# FPGA_Expansion.net
KiCad netlist of a schematic drawn in Altium Designer
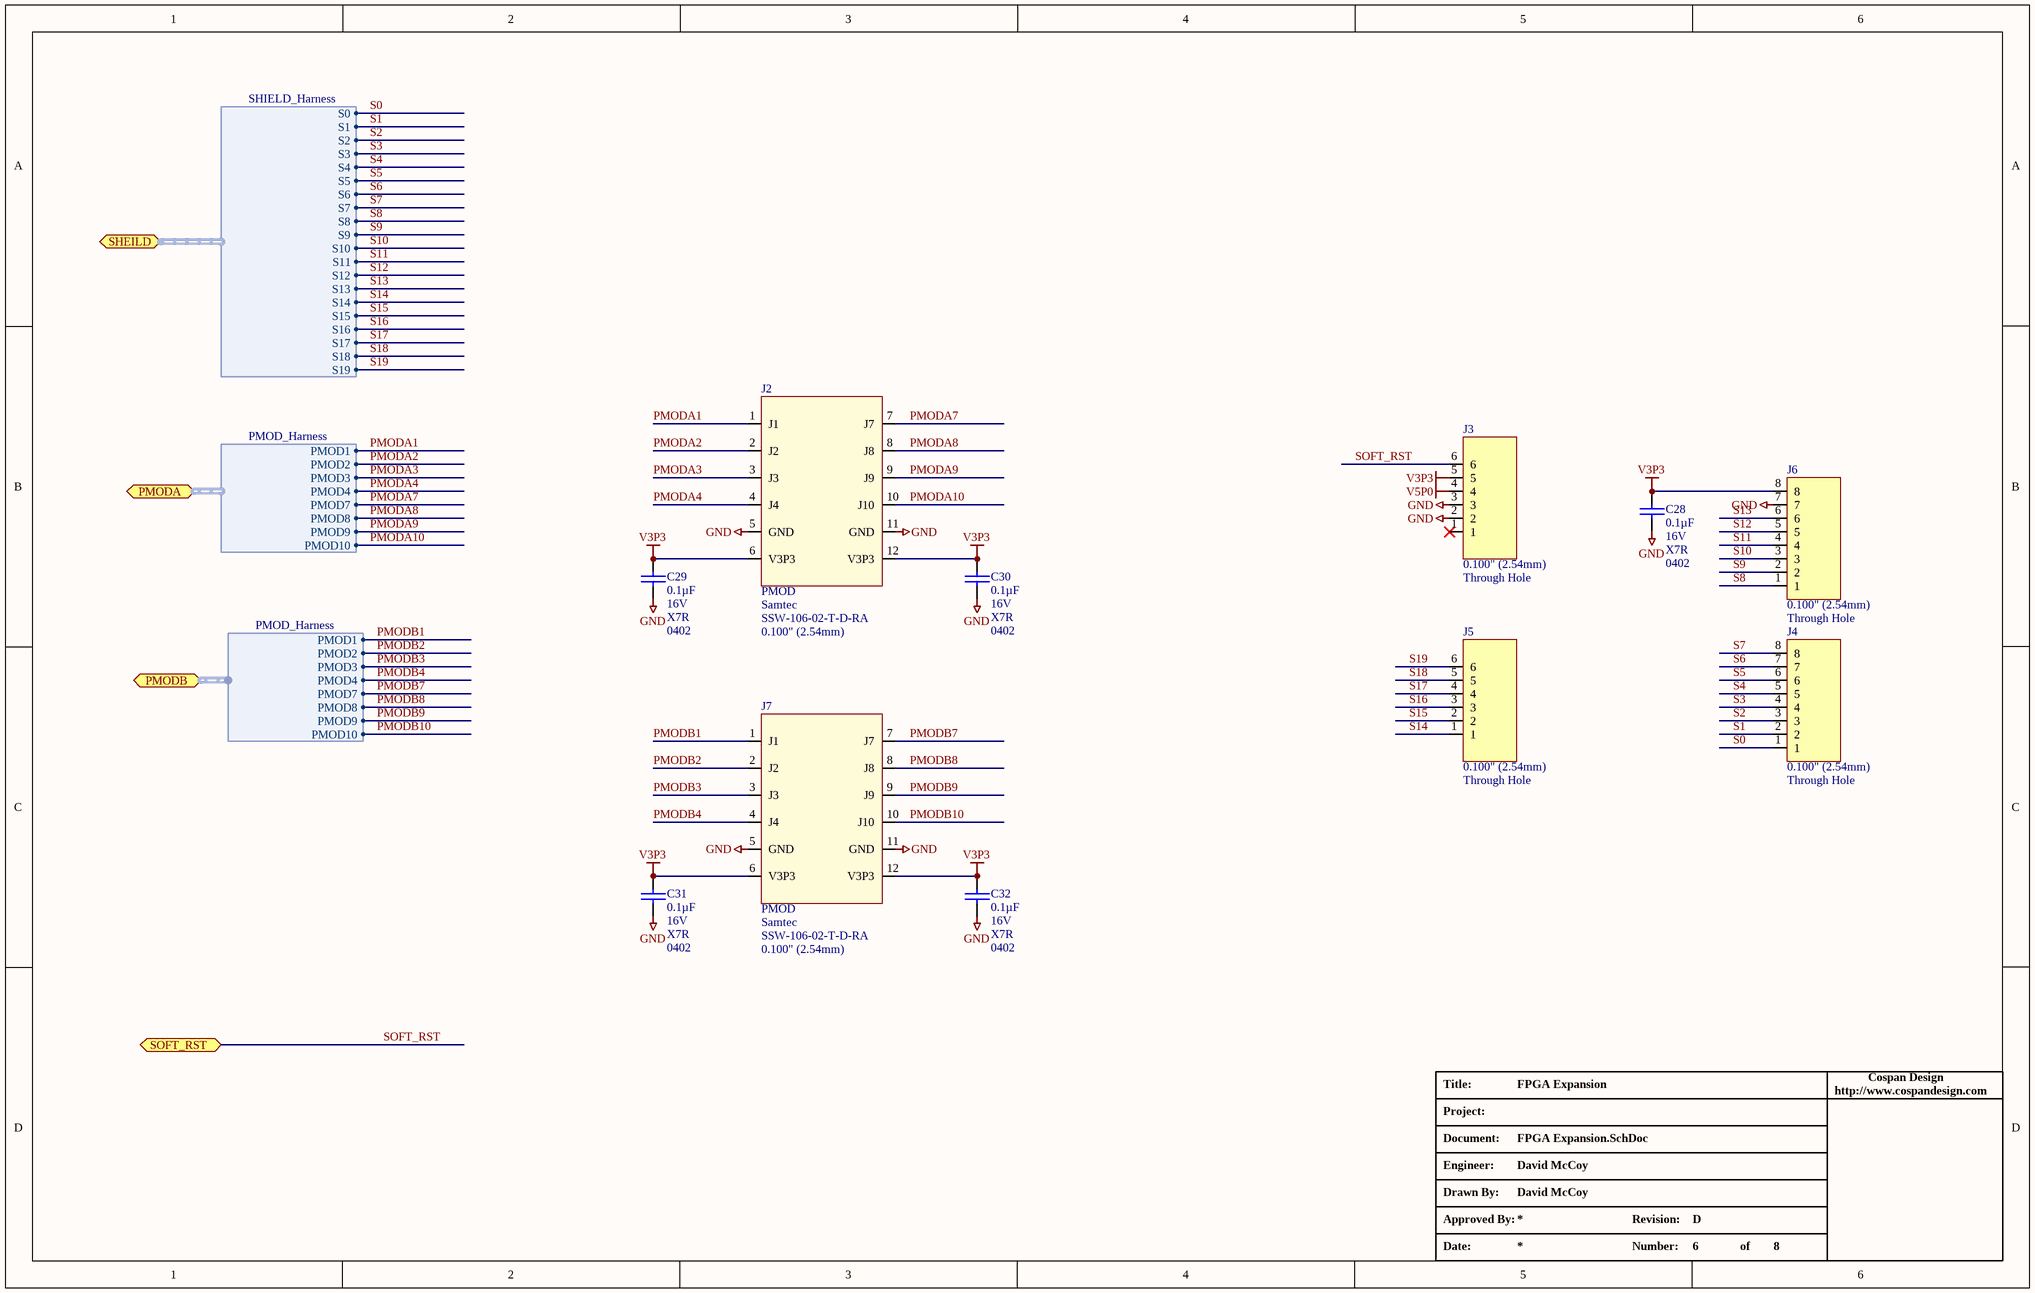
[diagram p0: FPGA Expansion.SchDoc]

(export (version "E")
  (design (tool "Eeschema 10.0.6"))
  (components
    (comp (ref "C28")
      (value "0.1uF")
      (footprint "C_ERA-0402")
      (description "CAP CER .10UF 16V X7R 0402")
      (fields
        (field (name "MANUFACTURER") "TDK Corporation")
        (field (name "MANUFACTURER PART NUMBER") "C1005X7R1C104K")
        (field (name "CAPACITANCE") "0.1µF")
        (field (name "VOLTAGE - RATED") "16V")
        (field (name "TEMPERATURE COEFFICIENT") "X7R")
        (field (name "PACKAGE / CASE") "0402")
      )
      (libsource (lib "Main LibraryX") (part "C_0402_0.1UF_16V"))
    )
    (comp (ref "C29")
      (value "0.1uF")
      (footprint "C_ERA-0402")
      (description "CAP CER .10UF 16V X7R 0402")
      (fields
        (field (name "MANUFACTURER") "TDK Corporation")
        (field (name "MANUFACTURER PART NUMBER") "C1005X7R1C104K")
        (field (name "CAPACITANCE") "0.1µF")
        (field (name "VOLTAGE - RATED") "16V")
        (field (name "TEMPERATURE COEFFICIENT") "X7R")
        (field (name "PACKAGE / CASE") "0402")
      )
      (libsource (lib "Main LibraryX") (part "C_0402_0.1UF_16V"))
    )
    (comp (ref "C30")
      (value "0.1uF")
      (footprint "C_ERA-0402")
      (description "CAP CER .10UF 16V X7R 0402")
      (fields
        (field (name "MANUFACTURER") "TDK Corporation")
        (field (name "MANUFACTURER PART NUMBER") "C1005X7R1C104K")
        (field (name "CAPACITANCE") "0.1µF")
        (field (name "VOLTAGE - RATED") "16V")
        (field (name "TEMPERATURE COEFFICIENT") "X7R")
        (field (name "PACKAGE / CASE") "0402")
      )
      (libsource (lib "Main LibraryX") (part "C_0402_0.1UF_16V"))
    )
    (comp (ref "C31")
      (value "0.1uF")
      (footprint "C_ERA-0402")
      (description "CAP CER .10UF 16V X7R 0402")
      (fields
        (field (name "MANUFACTURER") "TDK Corporation")
        (field (name "MANUFACTURER PART NUMBER") "C1005X7R1C104K")
        (field (name "CAPACITANCE") "0.1µF")
        (field (name "VOLTAGE - RATED") "16V")
        (field (name "TEMPERATURE COEFFICIENT") "X7R")
        (field (name "PACKAGE / CASE") "0402")
      )
      (libsource (lib "Main LibraryX") (part "C_0402_0.1UF_16V"))
    )
    (comp (ref "C32")
      (value "0.1uF")
      (footprint "C_ERA-0402")
      (description "CAP CER .10UF 16V X7R 0402")
      (fields
        (field (name "MANUFACTURER") "TDK Corporation")
        (field (name "MANUFACTURER PART NUMBER") "C1005X7R1C104K")
        (field (name "CAPACITANCE") "0.1µF")
        (field (name "VOLTAGE - RATED") "16V")
        (field (name "TEMPERATURE COEFFICIENT") "X7R")
        (field (name "PACKAGE / CASE") "0402")
      )
      (libsource (lib "Main LibraryX") (part "C_0402_0.1UF_16V"))
    )
    (comp (ref "J2")
      (value "PMOD")
      (footprint "PMOD")
      (description "CONN FEMALE 12POS DL .1\" R/A TIN")
      (fields
        (field (name "MANUFACTURER") "Samtec")
        (field (name "MANUFACTURER PART NUMBER") "SSW-106-02-T-D-RA")
        (field (name "PITCH") "0.100\" (2.54mm)")
      )
      (libsource (lib "Main LibraryX") (part "J_PMOD"))
    )
    (comp (ref "J3")
      (value "J_HDR1X6_THRHOLE_VERT_FEMALE")
      (footprint "HDR_1X6 - FEMALE")
      (description "CONN HEADER FEMALE 6POS .1\" TIN")
      (fields
        (field (name "MANUFACTURER") "Samtec")
        (field (name "MANUFACTURER PART NUMBER") "SSW-106-01-T-S")
        (field (name "PITCH") "0.100\" (2.54mm)")
        (field (name "MOUNTING TYPE") "Through Hole")
      )
      (libsource (lib "Main LibraryX") (part "J_HDR1X6_THRHOLE_VERT_FEMALE"))
    )
    (comp (ref "J4")
      (value "J_HDR1X8_THRHOLE_VERT_RECPT")
      (footprint "HDR_1X8 - FEMALE")
      (description "CONN HEADER FEMALE 8POS .1\" TIN")
      (fields
        (field (name "MANUFACTURER") "Samtec")
        (field (name "MANUFACTURER PART NUMBER") "SSW-108-01-T-S")
        (field (name "PITCH") "0.100\" (2.54mm)")
        (field (name "MOUNTING TYPE") "Through Hole")
      )
      (libsource (lib "Main LibraryX") (part "J_HDR1X8_THRHOLE_VERT_FEMALE"))
    )
    (comp (ref "J5")
      (value "J_HDR1X6_THRHOLE_VERT_FEMALE")
      (footprint "HDR_1X6 - FEMALE")
      (description "CONN HEADER FEMALE 6POS .1\" TIN")
      (fields
        (field (name "MANUFACTURER") "Samtec")
        (field (name "MANUFACTURER PART NUMBER") "SSW-106-01-T-S")
        (field (name "PITCH") "0.100\" (2.54mm)")
        (field (name "MOUNTING TYPE") "Through Hole")
      )
      (libsource (lib "Main LibraryX") (part "J_HDR1X6_THRHOLE_VERT_FEMALE"))
    )
    (comp (ref "J6")
      (value "J_HDR1X8_THRHOLE_VERT_RECPT")
      (footprint "HDR_1X8 - FEMALE")
      (description "CONN HEADER FEMALE 8POS .1\" TIN")
      (fields
        (field (name "MANUFACTURER") "Samtec")
        (field (name "MANUFACTURER PART NUMBER") "SSW-108-01-T-S")
        (field (name "PITCH") "0.100\" (2.54mm)")
        (field (name "MOUNTING TYPE") "Through Hole")
      )
      (libsource (lib "Main LibraryX") (part "J_HDR1X8_THRHOLE_VERT_FEMALE"))
    )
    (comp (ref "J7")
      (value "PMOD")
      (footprint "PMOD")
      (description "CONN FEMALE 12POS DL .1\" R/A TIN")
      (fields
        (field (name "MANUFACTURER") "Samtec")
        (field (name "MANUFACTURER PART NUMBER") "SSW-106-02-T-D-RA")
        (field (name "PITCH") "0.100\" (2.54mm)")
      )
      (libsource (lib "Main LibraryX") (part "J_PMOD"))
    )
  )
  (nets
    (net (code "3") (name "/PMODA1") (class "Default")
      (node (ref "J2") (pin "1") (pinfunction "J1_1") (pintype "passive"))
    )
    (net (code "4") (name "/PMODA2") (class "Default")
      (node (ref "J2") (pin "2") (pinfunction "J2_2") (pintype "passive"))
    )
    (net (code "5") (name "/PMODA3") (class "Default")
      (node (ref "J2") (pin "3") (pinfunction "J3_3") (pintype "passive"))
    )
    (net (code "6") (name "/PMODA4") (class "Default")
      (node (ref "J2") (pin "4") (pinfunction "J4_4") (pintype "passive"))
    )
    (net (code "7") (name "/PMODA7") (class "Default")
      (node (ref "J2") (pin "7") (pinfunction "J7_7") (pintype "passive"))
    )
    (net (code "8") (name "/PMODA8") (class "Default")
      (node (ref "J2") (pin "8") (pinfunction "J8_8") (pintype "passive"))
    )
    (net (code "9") (name "/PMODA9") (class "Default")
      (node (ref "J2") (pin "9") (pinfunction "J9_9") (pintype "passive"))
    )
    (net (code "10") (name "/PMODA10") (class "Default")
      (node (ref "J2") (pin "10") (pinfunction "J10_10") (pintype "passive"))
    )
    (net (code "11") (name "/PMODB1") (class "Default")
      (node (ref "J7") (pin "1") (pinfunction "J1_1") (pintype "passive"))
    )
    (net (code "12") (name "/PMODB2") (class "Default")
      (node (ref "J7") (pin "2") (pinfunction "J2_2") (pintype "passive"))
    )
    (net (code "13") (name "/PMODB3") (class "Default")
      (node (ref "J7") (pin "3") (pinfunction "J3_3") (pintype "passive"))
    )
    (net (code "14") (name "/PMODB4") (class "Default")
      (node (ref "J7") (pin "4") (pinfunction "J4_4") (pintype "passive"))
    )
    (net (code "15") (name "/PMODB7") (class "Default")
      (node (ref "J7") (pin "7") (pinfunction "J7_7") (pintype "passive"))
    )
    (net (code "16") (name "/PMODB8") (class "Default")
      (node (ref "J7") (pin "8") (pinfunction "J8_8") (pintype "passive"))
    )
    (net (code "17") (name "/PMODB9") (class "Default")
      (node (ref "J7") (pin "9") (pinfunction "J9_9") (pintype "passive"))
    )
    (net (code "18") (name "/PMODB10") (class "Default")
      (node (ref "J7") (pin "10") (pinfunction "J10_10") (pintype "passive"))
    )
    (net (code "19") (name "/S0") (class "Default")
      (node (ref "J4") (pin "1") (pinfunction "1_1") (pintype "passive"))
    )
    (net (code "20") (name "/S1") (class "Default")
      (node (ref "J4") (pin "2") (pinfunction "2_2") (pintype "passive"))
    )
    (net (code "21") (name "/S2") (class "Default")
      (node (ref "J4") (pin "3") (pinfunction "3_3") (pintype "passive"))
    )
    (net (code "22") (name "/S3") (class "Default")
      (node (ref "J4") (pin "4") (pinfunction "4_4") (pintype "passive"))
    )
    (net (code "23") (name "/S4") (class "Default")
      (node (ref "J4") (pin "5") (pinfunction "5_5") (pintype "passive"))
    )
    (net (code "24") (name "/S5") (class "Default")
      (node (ref "J4") (pin "6") (pinfunction "6_6") (pintype "passive"))
    )
    (net (code "25") (name "/S6") (class "Default")
      (node (ref "J4") (pin "7") (pinfunction "7_7") (pintype "passive"))
    )
    (net (code "26") (name "/S7") (class "Default")
      (node (ref "J4") (pin "8") (pinfunction "8_8") (pintype "passive"))
    )
    (net (code "27") (name "/S8") (class "Default")
      (node (ref "J6") (pin "1") (pinfunction "1_1") (pintype "passive"))
    )
    (net (code "28") (name "/S9") (class "Default")
      (node (ref "J6") (pin "2") (pinfunction "2_2") (pintype "passive"))
    )
    (net (code "29") (name "/S10") (class "Default")
      (node (ref "J6") (pin "3") (pinfunction "3_3") (pintype "passive"))
    )
    (net (code "30") (name "/S11") (class "Default")
      (node (ref "J6") (pin "4") (pinfunction "4_4") (pintype "passive"))
    )
    (net (code "31") (name "/S12") (class "Default")
      (node (ref "J6") (pin "5") (pinfunction "5_5") (pintype "passive"))
    )
    (net (code "32") (name "/S13") (class "Default")
      (node (ref "J6") (pin "6") (pinfunction "6_6") (pintype "passive"))
    )
    (net (code "33") (name "/S14") (class "Default")
      (node (ref "J5") (pin "1") (pinfunction "1_1") (pintype "passive"))
    )
    (net (code "34") (name "/S15") (class "Default")
      (node (ref "J5") (pin "2") (pinfunction "2_2") (pintype "passive"))
    )
    (net (code "35") (name "/S16") (class "Default")
      (node (ref "J5") (pin "3") (pinfunction "3_3") (pintype "passive"))
    )
    (net (code "36") (name "/S17") (class "Default")
      (node (ref "J5") (pin "4") (pinfunction "4_4") (pintype "passive"))
    )
    (net (code "37") (name "/S18") (class "Default")
      (node (ref "J5") (pin "5") (pinfunction "5_5") (pintype "passive"))
    )
    (net (code "38") (name "/S19") (class "Default")
      (node (ref "J5") (pin "6") (pinfunction "6_6") (pintype "passive"))
    )
    (net (code "39") (name "/SOFT_RST") (class "Default")
      (node (ref "J3") (pin "6") (pinfunction "6_6") (pintype "passive"))
    )
    (net (code "42") (name "GND") (class "Default")
      (node (ref "C28") (pin "1") (pinfunction "1_1") (pintype "passive"))
      (node (ref "C29") (pin "1") (pinfunction "1_1") (pintype "passive"))
      (node (ref "C30") (pin "1") (pinfunction "1_1") (pintype "passive"))
      (node (ref "C31") (pin "1") (pinfunction "1_1") (pintype "passive"))
      (node (ref "C32") (pin "1") (pinfunction "1_1") (pintype "passive"))
      (node (ref "J2") (pin "11") (pinfunction "GND_11") (pintype "passive"))
      (node (ref "J2") (pin "5") (pinfunction "GND_5") (pintype "passive"))
      (node (ref "J3") (pin "2") (pinfunction "2_2") (pintype "passive"))
      (node (ref "J3") (pin "3") (pinfunction "3_3") (pintype "passive"))
      (node (ref "J6") (pin "7") (pinfunction "7_7") (pintype "passive"))
      (node (ref "J7") (pin "11") (pinfunction "GND_11") (pintype "passive"))
      (node (ref "J7") (pin "5") (pinfunction "GND_5") (pintype "passive"))
    )
    (net (code "43") (name "V3P3") (class "Default")
      (node (ref "C28") (pin "2") (pinfunction "2_2") (pintype "passive"))
      (node (ref "C29") (pin "2") (pinfunction "2_2") (pintype "passive"))
      (node (ref "C30") (pin "2") (pinfunction "2_2") (pintype "passive"))
      (node (ref "C31") (pin "2") (pinfunction "2_2") (pintype "passive"))
      (node (ref "C32") (pin "2") (pinfunction "2_2") (pintype "passive"))
      (node (ref "J2") (pin "12") (pinfunction "V3P3_12") (pintype "passive"))
      (node (ref "J2") (pin "6") (pinfunction "V3P3_6") (pintype "passive"))
      (node (ref "J3") (pin "5") (pinfunction "5_5") (pintype "passive"))
      (node (ref "J6") (pin "8") (pinfunction "8_8") (pintype "passive"))
      (node (ref "J7") (pin "12") (pinfunction "V3P3_12") (pintype "passive"))
      (node (ref "J7") (pin "6") (pinfunction "V3P3_6") (pintype "passive"))
    )
    (net (code "44") (name "V5P0") (class "Default")
      (node (ref "J3") (pin "4") (pinfunction "4_4") (pintype "passive"))
    )
    (net (code "45") (name "unconnected-(J3-Pad1)") (class "Default")
      (node (ref "J3") (pin "1") (pinfunction "1_1") (pintype "passive+no_connect"))
    )
  )
)
